# MMMM_Bottom.net
KiCad netlist of a schematic drawn in EAGLE
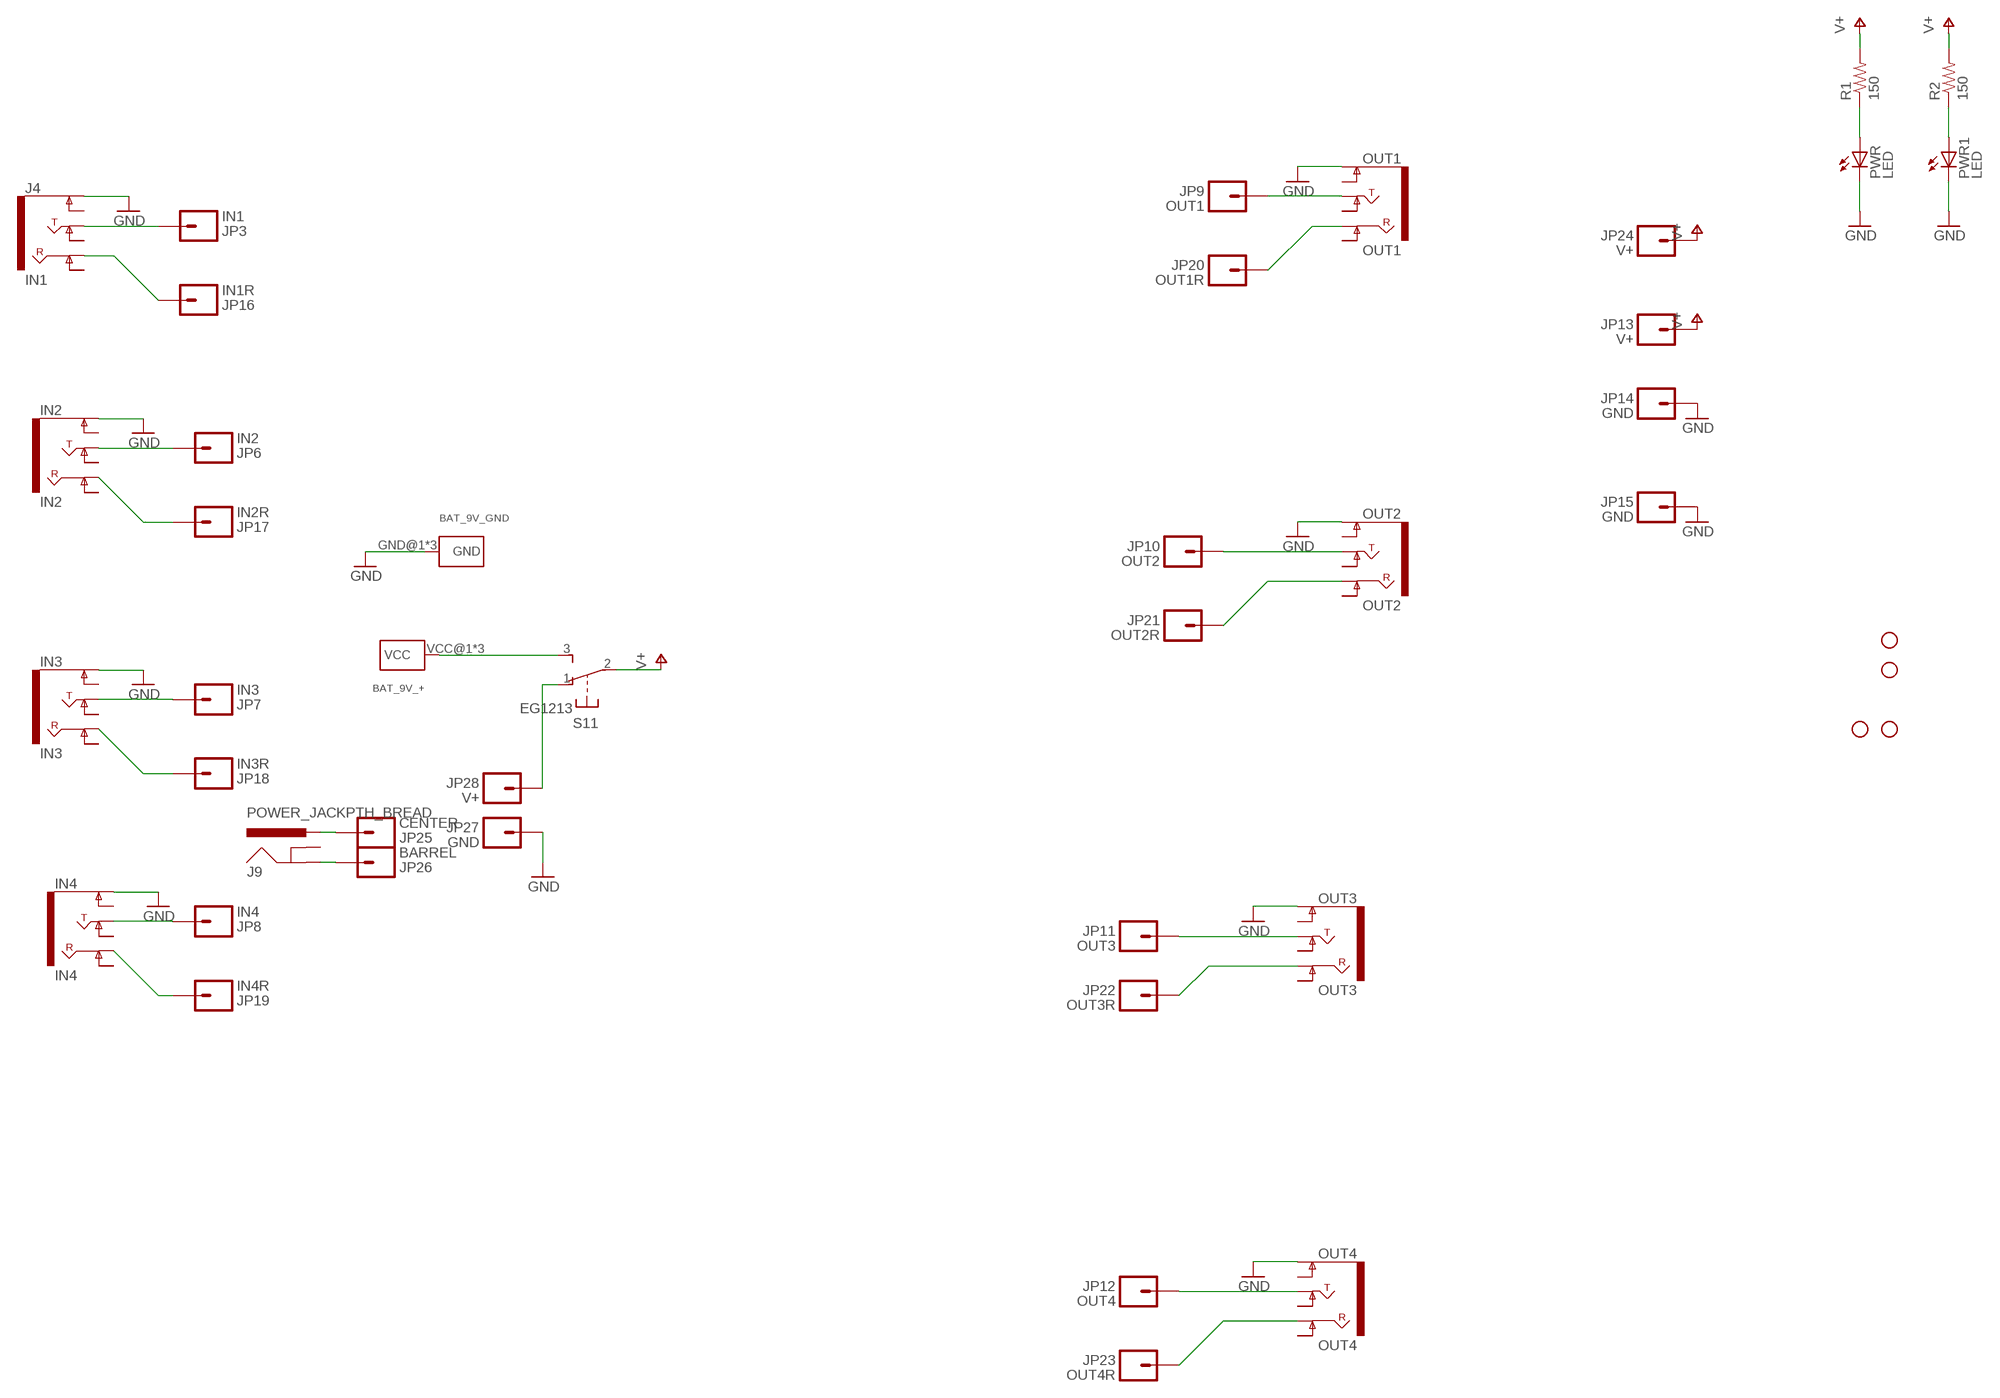
[diagram p0: schematic, sheet 1]

(export (version "E")
  (design (tool "Eeschema 10.0.6"))
  (components
    (comp (ref "BAT_9V_+")
      (value "KEYSTONE-637")
      (footprint "eagle-import:KEYSTONE_AA_AAA_BATTERY_TERMINAL-637")
      (libsource (lib "eagle-import") (part "KEYSTONE-637"))
    )
    (comp (ref "BAT_9V_GND")
      (value "KEYSTONE-629")
      (footprint "eagle-import:KEYSTONE_AA_AAA_BATTERY_TERMINAL-629")
      (libsource (lib "eagle-import") (part "KEYSTONE-629"))
    )
    (comp (ref "IN2")
      (value "IN2")
      (footprint "eagle-import:AUDIO-JACK-.25-INCH-HORIZ-PTH")
      (libsource (lib "eagle-import") (part "AUDIO-JACK4-.25-HORIZ-TRS"))
    )
    (comp (ref "IN3")
      (value "IN3")
      (footprint "eagle-import:AUDIO-JACK-.25-INCH-HORIZ-PTH")
      (libsource (lib "eagle-import") (part "AUDIO-JACK4-.25-HORIZ-TRS"))
    )
    (comp (ref "IN4")
      (value "IN4")
      (footprint "eagle-import:AUDIO-JACK-.25-INCH-HORIZ-PTH")
      (libsource (lib "eagle-import") (part "AUDIO-JACK4-.25-HORIZ-TRS"))
    )
    (comp (ref "J4")
      (value "IN1")
      (footprint "eagle-import:AUDIO-JACK-.25-INCH-HORIZ-PTH")
      (libsource (lib "eagle-import") (part "AUDIO-JACK4-.25-HORIZ-TRS"))
    )
    (comp (ref "J9")
      (value "POWER_JACKPTH_BREAD")
      (footprint "eagle-import:POWER_JACK_PTH_BREAD")
      (libsource (lib "eagle-import") (part "POWER_JACKPTH_BREAD"))
    )
    (comp (ref "JP1")
      (value "STAND-OFF")
      (footprint "eagle-import:STAND-OFF")
      (libsource (lib "eagle-import") (part "STAND-OFF"))
    )
    (comp (ref "JP2")
      (value "STAND-OFF")
      (footprint "eagle-import:STAND-OFF")
      (libsource (lib "eagle-import") (part "STAND-OFF"))
    )
    (comp (ref "JP3")
      (value "IN1")
      (footprint "eagle-import:1X01_SIDE_NAME")
      (libsource (lib "eagle-import") (part "HEADER-1X1"))
    )
    (comp (ref "JP4")
      (value "STAND-OFF")
      (footprint "eagle-import:STAND-OFF")
      (libsource (lib "eagle-import") (part "STAND-OFF"))
    )
    (comp (ref "JP5")
      (value "STAND-OFF")
      (footprint "eagle-import:STAND-OFF")
      (libsource (lib "eagle-import") (part "STAND-OFF"))
    )
    (comp (ref "JP6")
      (value "IN2")
      (footprint "eagle-import:1X01_SIDE_NAME")
      (libsource (lib "eagle-import") (part "HEADER-1X1"))
    )
    (comp (ref "JP7")
      (value "IN3")
      (footprint "eagle-import:1X01_SIDE_NAME")
      (libsource (lib "eagle-import") (part "HEADER-1X1"))
    )
    (comp (ref "JP8")
      (value "IN4")
      (footprint "eagle-import:1X01_SIDE_NAME")
      (libsource (lib "eagle-import") (part "HEADER-1X1"))
    )
    (comp (ref "JP9")
      (value "OUT1")
      (footprint "eagle-import:1X01_SIDE_NAME")
      (libsource (lib "eagle-import") (part "HEADER-1X1"))
    )
    (comp (ref "JP10")
      (value "OUT2")
      (footprint "eagle-import:1X01_SIDE_NAME")
      (libsource (lib "eagle-import") (part "HEADER-1X1"))
    )
    (comp (ref "JP11")
      (value "OUT3")
      (footprint "eagle-import:1X01_SIDE_NAME")
      (libsource (lib "eagle-import") (part "HEADER-1X1"))
    )
    (comp (ref "JP12")
      (value "OUT4")
      (footprint "eagle-import:1X01_SIDE_NAME")
      (libsource (lib "eagle-import") (part "HEADER-1X1"))
    )
    (comp (ref "JP13")
      (value "V+")
      (footprint "eagle-import:1X01_SIDE_NAME")
      (libsource (lib "eagle-import") (part "HEADER-1X1"))
    )
    (comp (ref "JP14")
      (value "GND")
      (footprint "eagle-import:1X01_SIDE_NAME")
      (libsource (lib "eagle-import") (part "HEADER-1X1"))
    )
    (comp (ref "JP15")
      (value "GND")
      (footprint "eagle-import:1X01_SIDE_NAME")
      (libsource (lib "eagle-import") (part "HEADER-1X1"))
    )
    (comp (ref "JP16")
      (value "IN1R")
      (footprint "eagle-import:1X01_SIDE_NAME")
      (libsource (lib "eagle-import") (part "HEADER-1X1"))
    )
    (comp (ref "JP17")
      (value "IN2R")
      (footprint "eagle-import:1X01_SIDE_NAME")
      (libsource (lib "eagle-import") (part "HEADER-1X1"))
    )
    (comp (ref "JP18")
      (value "IN3R")
      (footprint "eagle-import:1X01_SIDE_NAME")
      (libsource (lib "eagle-import") (part "HEADER-1X1"))
    )
    (comp (ref "JP19")
      (value "IN4R")
      (footprint "eagle-import:1X01_SIDE_NAME")
      (libsource (lib "eagle-import") (part "HEADER-1X1"))
    )
    (comp (ref "JP20")
      (value "OUT1R")
      (footprint "eagle-import:1X01_SIDE_NAME")
      (libsource (lib "eagle-import") (part "HEADER-1X1"))
    )
    (comp (ref "JP21")
      (value "OUT2R")
      (footprint "eagle-import:1X01_SIDE_NAME")
      (libsource (lib "eagle-import") (part "HEADER-1X1"))
    )
    (comp (ref "JP22")
      (value "OUT3R")
      (footprint "eagle-import:1X01_SIDE_NAME")
      (libsource (lib "eagle-import") (part "HEADER-1X1"))
    )
    (comp (ref "JP23")
      (value "OUT4R")
      (footprint "eagle-import:1X01_SIDE_NAME")
      (libsource (lib "eagle-import") (part "HEADER-1X1"))
    )
    (comp (ref "JP24")
      (value "V+")
      (footprint "eagle-import:1X01_SIDE_NAME")
      (libsource (lib "eagle-import") (part "HEADER-1X1"))
    )
    (comp (ref "JP25")
      (value "CENTER")
      (footprint "eagle-import:1X01_SIDE_NAME_SML")
      (libsource (lib "eagle-import") (part "HEADER-1X11X01_SIDE_NAME_SML"))
    )
    (comp (ref "JP26")
      (value "BARREL")
      (footprint "eagle-import:1X01_SIDE_NAME_SML")
      (libsource (lib "eagle-import") (part "HEADER-1X11X01_SIDE_NAME_SML"))
    )
    (comp (ref "JP27")
      (value "GND")
      (footprint "eagle-import:1X01_SIDE_NAME_SML")
      (libsource (lib "eagle-import") (part "HEADER-1X11X01_SIDE_NAME_SML"))
    )
    (comp (ref "JP28")
      (value "V+")
      (footprint "eagle-import:1X01_SIDE_NAME_SML")
      (libsource (lib "eagle-import") (part "HEADER-1X11X01_SIDE_NAME_SML"))
    )
    (comp (ref "OUT1")
      (value "OUT1")
      (footprint "eagle-import:AUDIO-JACK-.25-INCH-HORIZ-PTH")
      (libsource (lib "eagle-import") (part "AUDIO-JACK4-.25-HORIZ-TRS"))
    )
    (comp (ref "OUT2")
      (value "OUT2")
      (footprint "eagle-import:AUDIO-JACK-.25-INCH-HORIZ-PTH")
      (libsource (lib "eagle-import") (part "AUDIO-JACK4-.25-HORIZ-TRS"))
    )
    (comp (ref "OUT3")
      (value "OUT3")
      (footprint "eagle-import:AUDIO-JACK-.25-INCH-HORIZ-PTH")
      (libsource (lib "eagle-import") (part "AUDIO-JACK4-.25-HORIZ-TRS"))
    )
    (comp (ref "OUT4")
      (value "OUT4")
      (footprint "eagle-import:AUDIO-JACK-.25-INCH-HORIZ-PTH")
      (libsource (lib "eagle-import") (part "AUDIO-JACK4-.25-HORIZ-TRS"))
    )
    (comp (ref "PWR")
      (value "LED")
      (footprint "eagle-import:LED3MM-MINUS")
      (libsource (lib "eagle-import") (part "LED-3MM-MINUS"))
    )
    (comp (ref "PWR1")
      (value "LED")
      (footprint "eagle-import:LED3MM-MINUS")
      (libsource (lib "eagle-import") (part "LED-3MM-MINUS"))
    )
    (comp (ref "R1")
      (value "150")
      (footprint "eagle-import:0204_5")
      (libsource (lib "eagle-import") (part "R-US_0204/5"))
    )
    (comp (ref "R2")
      (value "150")
      (footprint "eagle-import:0204_5")
      (libsource (lib "eagle-import") (part "R-US_0204/5"))
    )
    (comp (ref "S1")
      (value "EG1213")
      (footprint "eagle-import:EG1213")
      (libsource (lib "eagle-import") (part "EG1213"))
    )
  )
  (nets
    (net (code "1") (name "GND") (class "Default")
      (node (ref "BAT_9V_GND") (pin "GND@1") (pinfunction "GND_GND@1") (pintype "power_in"))
      (node (ref "BAT_9V_GND") (pin "GND@2") (pinfunction "GND_GND@2") (pintype "power_in"))
      (node (ref "BAT_9V_GND") (pin "GND@3") (pinfunction "GND_GND@3") (pintype "power_in"))
      (node (ref "IN2") (pin "SLEEVE") (pinfunction "EARTH_SLEEVE") (pintype "bidirectional"))
      (node (ref "IN3") (pin "SLEEVE") (pinfunction "EARTH_SLEEVE") (pintype "bidirectional"))
      (node (ref "IN4") (pin "SLEEVE") (pinfunction "EARTH_SLEEVE") (pintype "bidirectional"))
      (node (ref "J4") (pin "SLEEVE") (pinfunction "EARTH_SLEEVE") (pintype "bidirectional"))
      (node (ref "JP14") (pin "1") (pinfunction "1_1") (pintype "passive"))
      (node (ref "JP15") (pin "1") (pinfunction "1_1") (pintype "passive"))
      (node (ref "JP27") (pin "1") (pinfunction "1_1") (pintype "passive"))
      (node (ref "OUT1") (pin "SLEEVE") (pinfunction "EARTH_SLEEVE") (pintype "bidirectional"))
      (node (ref "OUT2") (pin "SLEEVE") (pinfunction "EARTH_SLEEVE") (pintype "bidirectional"))
      (node (ref "OUT3") (pin "SLEEVE") (pinfunction "EARTH_SLEEVE") (pintype "bidirectional"))
      (node (ref "OUT4") (pin "SLEEVE") (pinfunction "EARTH_SLEEVE") (pintype "bidirectional"))
      (node (ref "PWR") (pin "K") (pinfunction "C_K") (pintype "passive"))
      (node (ref "PWR1") (pin "K") (pinfunction "C_K") (pintype "passive"))
    )
    (net (code "2") (name "Net-(IN2-PadRING)") (class "Default")
      (node (ref "IN2") (pin "RING") (pinfunction "RING_RING") (pintype "bidirectional"))
      (node (ref "JP17") (pin "1") (pinfunction "1_1") (pintype "passive"))
    )
    (net (code "3") (name "Net-(IN2-PadTIP)") (class "Default")
      (node (ref "IN2") (pin "TIP") (pinfunction "TIP_TIP") (pintype "bidirectional"))
      (node (ref "JP6") (pin "1") (pinfunction "1_1") (pintype "passive"))
    )
    (net (code "4") (name "Net-(IN3-PadRING)") (class "Default")
      (node (ref "IN3") (pin "RING") (pinfunction "RING_RING") (pintype "bidirectional"))
      (node (ref "JP18") (pin "1") (pinfunction "1_1") (pintype "passive"))
    )
    (net (code "5") (name "Net-(IN3-PadTIP)") (class "Default")
      (node (ref "IN3") (pin "TIP") (pinfunction "TIP_TIP") (pintype "bidirectional"))
      (node (ref "JP7") (pin "1") (pinfunction "1_1") (pintype "passive"))
    )
    (net (code "6") (name "Net-(IN4-PadRING)") (class "Default")
      (node (ref "IN4") (pin "RING") (pinfunction "RING_RING") (pintype "bidirectional"))
      (node (ref "JP19") (pin "1") (pinfunction "1_1") (pintype "passive"))
    )
    (net (code "7") (name "Net-(IN4-PadTIP)") (class "Default")
      (node (ref "IN4") (pin "TIP") (pinfunction "TIP_TIP") (pintype "bidirectional"))
      (node (ref "JP8") (pin "1") (pinfunction "1_1") (pintype "passive"))
    )
    (net (code "8") (name "Net-(J4-PadRING)") (class "Default")
      (node (ref "J4") (pin "RING") (pinfunction "RING_RING") (pintype "bidirectional"))
      (node (ref "JP16") (pin "1") (pinfunction "1_1") (pintype "passive"))
    )
    (net (code "9") (name "Net-(J4-PadTIP)") (class "Default")
      (node (ref "J4") (pin "TIP") (pinfunction "TIP_TIP") (pintype "bidirectional"))
      (node (ref "JP3") (pin "1") (pinfunction "1_1") (pintype "passive"))
    )
    (net (code "10") (name "Net-(J9-PadGND)") (class "Default")
      (node (ref "J9") (pin "GND") (pinfunction "GND_GND") (pintype "bidirectional"))
      (node (ref "JP26") (pin "1") (pinfunction "1_1") (pintype "passive"))
    )
    (net (code "11") (name "Net-(J9-PadPWR)") (class "Default")
      (node (ref "J9") (pin "PWR") (pinfunction "PWR_PWR") (pintype "bidirectional"))
      (node (ref "JP25") (pin "1") (pinfunction "1_1") (pintype "passive"))
    )
    (net (code "12") (name "Net-(JP9-Pad1)") (class "Default")
      (node (ref "JP9") (pin "1") (pinfunction "1_1") (pintype "passive"))
      (node (ref "OUT1") (pin "TIP") (pinfunction "TIP_TIP") (pintype "bidirectional"))
    )
    (net (code "13") (name "Net-(JP10-Pad1)") (class "Default")
      (node (ref "JP10") (pin "1") (pinfunction "1_1") (pintype "passive"))
      (node (ref "OUT2") (pin "TIP") (pinfunction "TIP_TIP") (pintype "bidirectional"))
    )
    (net (code "14") (name "Net-(JP11-Pad1)") (class "Default")
      (node (ref "JP11") (pin "1") (pinfunction "1_1") (pintype "passive"))
      (node (ref "OUT3") (pin "TIP") (pinfunction "TIP_TIP") (pintype "bidirectional"))
    )
    (net (code "15") (name "Net-(JP12-Pad1)") (class "Default")
      (node (ref "JP12") (pin "1") (pinfunction "1_1") (pintype "passive"))
      (node (ref "OUT4") (pin "TIP") (pinfunction "TIP_TIP") (pintype "bidirectional"))
    )
    (net (code "16") (name "Net-(JP20-Pad1)") (class "Default")
      (node (ref "JP20") (pin "1") (pinfunction "1_1") (pintype "passive"))
      (node (ref "OUT1") (pin "RING") (pinfunction "RING_RING") (pintype "bidirectional"))
    )
    (net (code "17") (name "Net-(JP21-Pad1)") (class "Default")
      (node (ref "JP21") (pin "1") (pinfunction "1_1") (pintype "passive"))
      (node (ref "OUT2") (pin "RING") (pinfunction "RING_RING") (pintype "bidirectional"))
    )
    (net (code "18") (name "Net-(JP22-Pad1)") (class "Default")
      (node (ref "JP22") (pin "1") (pinfunction "1_1") (pintype "passive"))
      (node (ref "OUT3") (pin "RING") (pinfunction "RING_RING") (pintype "bidirectional"))
    )
    (net (code "19") (name "Net-(JP23-Pad1)") (class "Default")
      (node (ref "JP23") (pin "1") (pinfunction "1_1") (pintype "passive"))
      (node (ref "OUT4") (pin "RING") (pinfunction "RING_RING") (pintype "bidirectional"))
    )
    (net (code "20") (name "Net-(PWR-PadA)") (class "Default")
      (node (ref "PWR") (pin "A") (pinfunction "A_A") (pintype "passive"))
      (node (ref "R1") (pin "1") (pinfunction "1_1") (pintype "passive"))
    )
    (net (code "21") (name "Net-(PWR1-PadA)") (class "Default")
      (node (ref "PWR1") (pin "A") (pinfunction "A_A") (pintype "passive"))
      (node (ref "R2") (pin "1") (pinfunction "1_1") (pintype "passive"))
    )
    (net (code "22") (name "Net-(S1A-O)") (class "Default")
      (node (ref "JP28") (pin "1") (pinfunction "1_1") (pintype "passive"))
      (node (ref "S1") (pin "1") (pinfunction "O_1") (pintype "passive"))
    )
    (net (code "23") (name "Net-(S1A-S)") (class "Default")
      (node (ref "BAT_9V_+") (pin "VCC@1") (pinfunction "VCC_VCC@1") (pintype "power_in"))
      (node (ref "BAT_9V_+") (pin "VCC@2") (pinfunction "VCC_VCC@2") (pintype "power_in"))
      (node (ref "BAT_9V_+") (pin "VCC@3") (pinfunction "VCC_VCC@3") (pintype "power_in"))
      (node (ref "S1") (pin "3") (pinfunction "S_3") (pintype "passive"))
    )
    (net (code "24") (name "V+") (class "Default")
      (node (ref "JP13") (pin "1") (pinfunction "1_1") (pintype "passive"))
      (node (ref "JP24") (pin "1") (pinfunction "1_1") (pintype "passive"))
      (node (ref "R1") (pin "2") (pinfunction "2_2") (pintype "passive"))
      (node (ref "R2") (pin "2") (pinfunction "2_2") (pintype "passive"))
      (node (ref "S1") (pin "2") (pinfunction "P_2") (pintype "passive"))
    )
    (net (code "25") (name "unconnected-(IN2-EARTH-NORM-PadSLEEVE-NORM)") (class "Default")
      (node (ref "IN2") (pin "SLEEVE-NORM") (pinfunction "EARTH-NORM_SLEEVE-NORM") (pintype "bidirectional"))
    )
    (net (code "26") (name "unconnected-(IN2-PadRING-NORM)") (class "Default")
      (node (ref "IN2") (pin "RING-NORM") (pinfunction "RING-NORM_RING-NORM") (pintype "bidirectional"))
    )
    (net (code "27") (name "unconnected-(IN2-PadTIP-NORM)") (class "Default")
      (node (ref "IN2") (pin "TIP-NORM") (pinfunction "TIP-NORM_TIP-NORM") (pintype "bidirectional"))
    )
    (net (code "28") (name "unconnected-(IN3-EARTH-NORM-PadSLEEVE-NORM)") (class "Default")
      (node (ref "IN3") (pin "SLEEVE-NORM") (pinfunction "EARTH-NORM_SLEEVE-NORM") (pintype "bidirectional"))
    )
    (net (code "29") (name "unconnected-(IN3-PadRING-NORM)") (class "Default")
      (node (ref "IN3") (pin "RING-NORM") (pinfunction "RING-NORM_RING-NORM") (pintype "bidirectional"))
    )
    (net (code "30") (name "unconnected-(IN3-PadTIP-NORM)") (class "Default")
      (node (ref "IN3") (pin "TIP-NORM") (pinfunction "TIP-NORM_TIP-NORM") (pintype "bidirectional"))
    )
    (net (code "31") (name "unconnected-(IN4-EARTH-NORM-PadSLEEVE-NORM)") (class "Default")
      (node (ref "IN4") (pin "SLEEVE-NORM") (pinfunction "EARTH-NORM_SLEEVE-NORM") (pintype "bidirectional"))
    )
    (net (code "32") (name "unconnected-(IN4-PadRING-NORM)") (class "Default")
      (node (ref "IN4") (pin "RING-NORM") (pinfunction "RING-NORM_RING-NORM") (pintype "bidirectional"))
    )
    (net (code "33") (name "unconnected-(IN4-PadTIP-NORM)") (class "Default")
      (node (ref "IN4") (pin "TIP-NORM") (pinfunction "TIP-NORM_TIP-NORM") (pintype "bidirectional"))
    )
    (net (code "34") (name "unconnected-(J4-EARTH-NORM-PadSLEEVE-NORM)") (class "Default")
      (node (ref "J4") (pin "SLEEVE-NORM") (pinfunction "EARTH-NORM_SLEEVE-NORM") (pintype "bidirectional"))
    )
    (net (code "35") (name "unconnected-(J4-PadRING-NORM)") (class "Default")
      (node (ref "J4") (pin "RING-NORM") (pinfunction "RING-NORM_RING-NORM") (pintype "bidirectional"))
    )
    (net (code "36") (name "unconnected-(J4-PadTIP-NORM)") (class "Default")
      (node (ref "J4") (pin "TIP-NORM") (pinfunction "TIP-NORM_TIP-NORM") (pintype "bidirectional"))
    )
    (net (code "37") (name "unconnected-(J9-PadGNDBREAK)") (class "Default")
      (node (ref "J9") (pin "GNDBREAK") (pinfunction "GNDBREAK_GNDBREAK") (pintype "bidirectional"))
    )
    (net (code "38") (name "unconnected-(OUT1-EARTH-NORM-PadSLEEVE-NORM)") (class "Default")
      (node (ref "OUT1") (pin "SLEEVE-NORM") (pinfunction "EARTH-NORM_SLEEVE-NORM") (pintype "bidirectional"))
    )
    (net (code "39") (name "unconnected-(OUT1-PadRING-NORM)") (class "Default")
      (node (ref "OUT1") (pin "RING-NORM") (pinfunction "RING-NORM_RING-NORM") (pintype "bidirectional"))
    )
    (net (code "40") (name "unconnected-(OUT1-PadTIP-NORM)") (class "Default")
      (node (ref "OUT1") (pin "TIP-NORM") (pinfunction "TIP-NORM_TIP-NORM") (pintype "bidirectional"))
    )
    (net (code "41") (name "unconnected-(OUT2-EARTH-NORM-PadSLEEVE-NORM)") (class "Default")
      (node (ref "OUT2") (pin "SLEEVE-NORM") (pinfunction "EARTH-NORM_SLEEVE-NORM") (pintype "bidirectional"))
    )
    (net (code "42") (name "unconnected-(OUT2-PadRING-NORM)") (class "Default")
      (node (ref "OUT2") (pin "RING-NORM") (pinfunction "RING-NORM_RING-NORM") (pintype "bidirectional"))
    )
    (net (code "43") (name "unconnected-(OUT2-PadTIP-NORM)") (class "Default")
      (node (ref "OUT2") (pin "TIP-NORM") (pinfunction "TIP-NORM_TIP-NORM") (pintype "bidirectional"))
    )
    (net (code "44") (name "unconnected-(OUT3-EARTH-NORM-PadSLEEVE-NORM)") (class "Default")
      (node (ref "OUT3") (pin "SLEEVE-NORM") (pinfunction "EARTH-NORM_SLEEVE-NORM") (pintype "bidirectional"))
    )
    (net (code "45") (name "unconnected-(OUT3-PadRING-NORM)") (class "Default")
      (node (ref "OUT3") (pin "RING-NORM") (pinfunction "RING-NORM_RING-NORM") (pintype "bidirectional"))
    )
    (net (code "46") (name "unconnected-(OUT3-PadTIP-NORM)") (class "Default")
      (node (ref "OUT3") (pin "TIP-NORM") (pinfunction "TIP-NORM_TIP-NORM") (pintype "bidirectional"))
    )
    (net (code "47") (name "unconnected-(OUT4-EARTH-NORM-PadSLEEVE-NORM)") (class "Default")
      (node (ref "OUT4") (pin "SLEEVE-NORM") (pinfunction "EARTH-NORM_SLEEVE-NORM") (pintype "bidirectional"))
    )
    (net (code "48") (name "unconnected-(OUT4-PadRING-NORM)") (class "Default")
      (node (ref "OUT4") (pin "RING-NORM") (pinfunction "RING-NORM_RING-NORM") (pintype "bidirectional"))
    )
    (net (code "49") (name "unconnected-(OUT4-PadTIP-NORM)") (class "Default")
      (node (ref "OUT4") (pin "TIP-NORM") (pinfunction "TIP-NORM_TIP-NORM") (pintype "bidirectional"))
    )
  )
)
